# Zio_Eink_Display_1_54.net
KiCad netlist of a schematic drawn in EAGLE
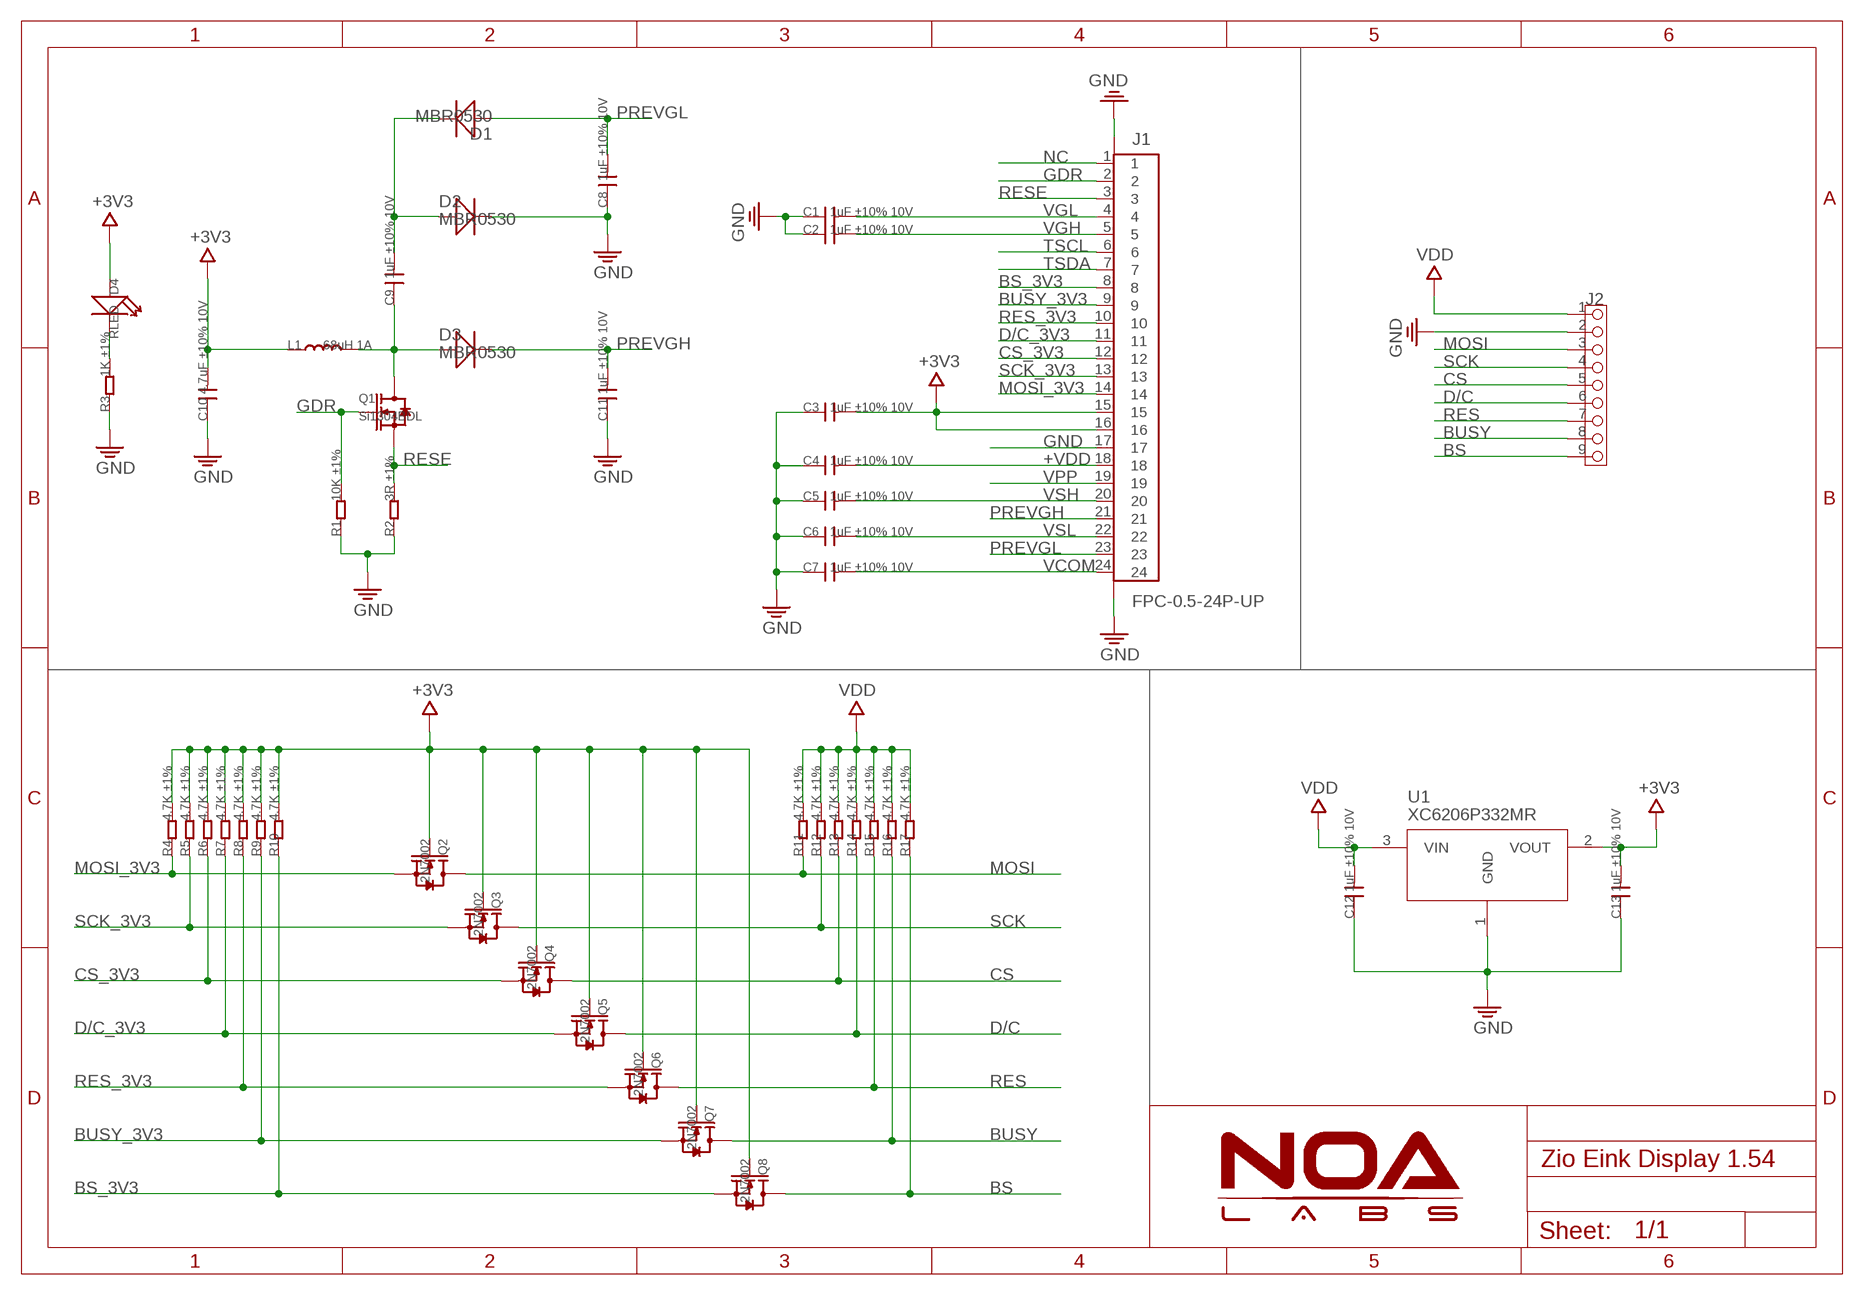
[diagram p0: schematic, sheet 1]

(export (version "E")
  (design (tool "Eeschema 10.0.6"))
  (components
    (comp (ref "C1")
      (value "1uF ±10% 10V")
      (footprint "eagle-import:0603")
      (libsource (lib "eagle-import") (part "C-0603"))
    )
    (comp (ref "C2")
      (value "1uF ±10% 10V")
      (footprint "eagle-import:0603")
      (libsource (lib "eagle-import") (part "C-0603"))
    )
    (comp (ref "C3")
      (value "1uF ±10% 10V")
      (footprint "eagle-import:0603")
      (libsource (lib "eagle-import") (part "C-0603"))
    )
    (comp (ref "C4")
      (value "1uF ±10% 10V")
      (footprint "eagle-import:0603")
      (libsource (lib "eagle-import") (part "C-0603"))
    )
    (comp (ref "C5")
      (value "1uF ±10% 10V")
      (footprint "eagle-import:0603")
      (libsource (lib "eagle-import") (part "C-0603"))
    )
    (comp (ref "C6")
      (value "1uF ±10% 10V")
      (footprint "eagle-import:0603")
      (libsource (lib "eagle-import") (part "C-0603"))
    )
    (comp (ref "C7")
      (value "1uF ±10% 10V")
      (footprint "eagle-import:0603")
      (libsource (lib "eagle-import") (part "C-0603"))
    )
    (comp (ref "C8")
      (value "1uF ±10% 10V")
      (footprint "eagle-import:0603")
      (libsource (lib "eagle-import") (part "C-0603"))
    )
    (comp (ref "C9")
      (value "1uF ±10% 10V")
      (footprint "eagle-import:0603")
      (libsource (lib "eagle-import") (part "C-0603"))
    )
    (comp (ref "C10")
      (value "4.7uF ±10% 10V")
      (footprint "eagle-import:0603")
      (libsource (lib "eagle-import") (part "C-0603"))
    )
    (comp (ref "C11")
      (value "1uF ±10% 10V")
      (footprint "eagle-import:0603")
      (libsource (lib "eagle-import") (part "C-0603"))
    )
    (comp (ref "C12")
      (value "1uF ±10% 10V")
      (footprint "eagle-import:0603")
      (libsource (lib "eagle-import") (part "C-0603"))
    )
    (comp (ref "C13")
      (value "1uF ±10% 10V")
      (footprint "eagle-import:0603")
      (libsource (lib "eagle-import") (part "C-0603"))
    )
    (comp (ref "D1")
      (value "MBR0530")
      (footprint "eagle-import:SOD123")
      (libsource (lib "eagle-import") (part "D'1206'"))
    )
    (comp (ref "D2")
      (value "MBR0530")
      (footprint "eagle-import:SOD123")
      (libsource (lib "eagle-import") (part "D'1206'"))
    )
    (comp (ref "D3")
      (value "MBR0530")
      (footprint "eagle-import:SOD123")
      (libsource (lib "eagle-import") (part "D'1206'"))
    )
    (comp (ref "D4")
      (value "RLED")
      (footprint "eagle-import:LED-0603")
      (libsource (lib "eagle-import") (part "LED'0603'"))
    )
    (comp (ref "J1")
      (value "FPC-0.5-24P-UP")
      (footprint "eagle-import:FPC-0.5-24P_UP")
      (libsource (lib "eagle-import") (part "FPC-0.5-24P-UP"))
    )
    (comp (ref "J2")
      (value "HEADER-9P2.54")
      (footprint "eagle-import:9P-2.54-SMD")
      (libsource (lib "eagle-import") (part "HEADER-9P2.54"))
    )
    (comp (ref "L1")
      (value "68uH 1A")
      (footprint "eagle-import:L3012")
      (libsource (lib "eagle-import") (part "L"))
    )
    (comp (ref "Q1")
      (value "Si1304BDL")
      (footprint "eagle-import:SOT-323")
      (libsource (lib "eagle-import") (part "MOSFET-N-323"))
    )
    (comp (ref "Q2")
      (value "2N7002")
      (footprint "eagle-import:SOT23")
      (libsource (lib "eagle-import") (part "MOSFET-N-SOT23"))
    )
    (comp (ref "Q3")
      (value "2N7002")
      (footprint "eagle-import:SOT23")
      (libsource (lib "eagle-import") (part "MOSFET-N-SOT23"))
    )
    (comp (ref "Q4")
      (value "2N7002")
      (footprint "eagle-import:SOT23")
      (libsource (lib "eagle-import") (part "MOSFET-N-SOT23"))
    )
    (comp (ref "Q5")
      (value "2N7002")
      (footprint "eagle-import:SOT23")
      (libsource (lib "eagle-import") (part "MOSFET-N-SOT23"))
    )
    (comp (ref "Q6")
      (value "2N7002")
      (footprint "eagle-import:SOT23")
      (libsource (lib "eagle-import") (part "MOSFET-N-SOT23"))
    )
    (comp (ref "Q7")
      (value "2N7002")
      (footprint "eagle-import:SOT23")
      (libsource (lib "eagle-import") (part "MOSFET-N-SOT23"))
    )
    (comp (ref "Q8")
      (value "2N7002")
      (footprint "eagle-import:SOT23")
      (libsource (lib "eagle-import") (part "MOSFET-N-SOT23"))
    )
    (comp (ref "R1")
      (value "10K ±1%")
      (footprint "eagle-import:0603")
      (libsource (lib "eagle-import") (part "R-0603"))
    )
    (comp (ref "R2")
      (value "3R ±1%")
      (footprint "eagle-import:0603")
      (libsource (lib "eagle-import") (part "R-0603"))
    )
    (comp (ref "R3")
      (value "1K ±1%")
      (footprint "eagle-import:0402")
      (libsource (lib "eagle-import") (part "R-0402"))
    )
    (comp (ref "R4")
      (value "4.7K ±1%")
      (footprint "eagle-import:0402")
      (libsource (lib "eagle-import") (part "R-0402"))
    )
    (comp (ref "R5")
      (value "4.7K ±1%")
      (footprint "eagle-import:0402")
      (libsource (lib "eagle-import") (part "R-0402"))
    )
    (comp (ref "R6")
      (value "4.7K ±1%")
      (footprint "eagle-import:0402")
      (libsource (lib "eagle-import") (part "R-0402"))
    )
    (comp (ref "R7")
      (value "4.7K ±1%")
      (footprint "eagle-import:0402")
      (libsource (lib "eagle-import") (part "R-0402"))
    )
    (comp (ref "R8")
      (value "4.7K ±1%")
      (footprint "eagle-import:0402")
      (libsource (lib "eagle-import") (part "R-0402"))
    )
    (comp (ref "R9")
      (value "4.7K ±1%")
      (footprint "eagle-import:0402")
      (libsource (lib "eagle-import") (part "R-0402"))
    )
    (comp (ref "R10")
      (value "4.7K ±1%")
      (footprint "eagle-import:0402")
      (libsource (lib "eagle-import") (part "R-0402"))
    )
    (comp (ref "R11")
      (value "4.7K ±1%")
      (footprint "eagle-import:0402")
      (libsource (lib "eagle-import") (part "R-0402"))
    )
    (comp (ref "R12")
      (value "4.7K ±1%")
      (footprint "eagle-import:0402")
      (libsource (lib "eagle-import") (part "R-0402"))
    )
    (comp (ref "R13")
      (value "4.7K ±1%")
      (footprint "eagle-import:0402")
      (libsource (lib "eagle-import") (part "R-0402"))
    )
    (comp (ref "R14")
      (value "4.7K ±1%")
      (footprint "eagle-import:0402")
      (libsource (lib "eagle-import") (part "R-0402"))
    )
    (comp (ref "R15")
      (value "4.7K ±1%")
      (footprint "eagle-import:0402")
      (libsource (lib "eagle-import") (part "R-0402"))
    )
    (comp (ref "R16")
      (value "4.7K ±1%")
      (footprint "eagle-import:0402")
      (libsource (lib "eagle-import") (part "R-0402"))
    )
    (comp (ref "R17")
      (value "4.7K ±1%")
      (footprint "eagle-import:0402")
      (libsource (lib "eagle-import") (part "R-0402"))
    )
    (comp (ref "U1")
      (value "XC6206P332MR")
      (footprint "eagle-import:SOT23")
      (libsource (lib "eagle-import") (part "XC6206MR"))
    )
  )
  (nets
    (net (code "1") (name "+3V3") (class "Default")
      (node (ref "C10") (pin "2") (pinfunction "2_2") (pintype "passive"))
      (node (ref "C13") (pin "2") (pinfunction "2_2") (pintype "passive"))
      (node (ref "C3") (pin "2") (pinfunction "2_2") (pintype "passive"))
      (node (ref "D4") (pin "+") (pinfunction "+_+") (pintype "passive"))
      (node (ref "J1") (pin "15") (pinfunction "15_15") (pintype "bidirectional"))
      (node (ref "J1") (pin "16") (pinfunction "16_16") (pintype "bidirectional"))
      (node (ref "L1") (pin "P$1") (pinfunction "1_P$1") (pintype "passive"))
      (node (ref "Q2") (pin "1") (pinfunction "G_1") (pintype "passive"))
      (node (ref "Q3") (pin "1") (pinfunction "G_1") (pintype "passive"))
      (node (ref "Q4") (pin "1") (pinfunction "G_1") (pintype "passive"))
      (node (ref "Q5") (pin "1") (pinfunction "G_1") (pintype "passive"))
      (node (ref "Q6") (pin "1") (pinfunction "G_1") (pintype "passive"))
      (node (ref "Q7") (pin "1") (pinfunction "G_1") (pintype "passive"))
      (node (ref "Q8") (pin "1") (pinfunction "G_1") (pintype "passive"))
      (node (ref "R10") (pin "2") (pinfunction "2_2") (pintype "passive"))
      (node (ref "R4") (pin "2") (pinfunction "2_2") (pintype "passive"))
      (node (ref "R5") (pin "2") (pinfunction "2_2") (pintype "passive"))
      (node (ref "R6") (pin "2") (pinfunction "2_2") (pintype "passive"))
      (node (ref "R7") (pin "2") (pinfunction "2_2") (pintype "passive"))
      (node (ref "R8") (pin "2") (pinfunction "2_2") (pintype "passive"))
      (node (ref "R9") (pin "2") (pinfunction "2_2") (pintype "passive"))
      (node (ref "U1") (pin "2") (pinfunction "VOUT_2") (pintype "bidirectional"))
    )
    (net (code "2") (name "/+VDD") (class "Default")
      (node (ref "C4") (pin "2") (pinfunction "2_2") (pintype "passive"))
      (node (ref "J1") (pin "18") (pinfunction "18_18") (pintype "bidirectional"))
    )
    (net (code "3") (name "/BS") (class "Default")
      (node (ref "J2") (pin "9") (pinfunction "9_9") (pintype "bidirectional"))
      (node (ref "Q8") (pin "3") (pinfunction "D_3") (pintype "passive"))
      (node (ref "R17") (pin "1") (pinfunction "1_1") (pintype "passive"))
    )
    (net (code "4") (name "/BS_3V3") (class "Default")
      (node (ref "J1") (pin "8") (pinfunction "8_8") (pintype "bidirectional"))
      (node (ref "Q8") (pin "2") (pinfunction "S_2") (pintype "passive"))
      (node (ref "R10") (pin "1") (pinfunction "1_1") (pintype "passive"))
    )
    (net (code "5") (name "/BUSY") (class "Default")
      (node (ref "J2") (pin "8") (pinfunction "8_8") (pintype "bidirectional"))
      (node (ref "Q7") (pin "3") (pinfunction "D_3") (pintype "passive"))
      (node (ref "R16") (pin "1") (pinfunction "1_1") (pintype "passive"))
    )
    (net (code "6") (name "/BUSY_3V3") (class "Default")
      (node (ref "J1") (pin "9") (pinfunction "9_9") (pintype "bidirectional"))
      (node (ref "Q7") (pin "2") (pinfunction "S_2") (pintype "passive"))
      (node (ref "R9") (pin "1") (pinfunction "1_1") (pintype "passive"))
    )
    (net (code "7") (name "/CS") (class "Default")
      (node (ref "J2") (pin "5") (pinfunction "5_5") (pintype "bidirectional"))
      (node (ref "Q4") (pin "3") (pinfunction "D_3") (pintype "passive"))
      (node (ref "R13") (pin "1") (pinfunction "1_1") (pintype "passive"))
    )
    (net (code "8") (name "/CS_3V3") (class "Default")
      (node (ref "J1") (pin "12") (pinfunction "12_12") (pintype "bidirectional"))
      (node (ref "Q4") (pin "2") (pinfunction "S_2") (pintype "passive"))
      (node (ref "R6") (pin "1") (pinfunction "1_1") (pintype "passive"))
    )
    (net (code "9") (name "/D{slash}C") (class "Default")
      (node (ref "J2") (pin "6") (pinfunction "6_6") (pintype "bidirectional"))
      (node (ref "Q5") (pin "3") (pinfunction "D_3") (pintype "passive"))
      (node (ref "R14") (pin "1") (pinfunction "1_1") (pintype "passive"))
    )
    (net (code "10") (name "/D{slash}C_3V3") (class "Default")
      (node (ref "J1") (pin "11") (pinfunction "11_11") (pintype "bidirectional"))
      (node (ref "Q5") (pin "2") (pinfunction "S_2") (pintype "passive"))
      (node (ref "R7") (pin "1") (pinfunction "1_1") (pintype "passive"))
    )
    (net (code "11") (name "/GDR") (class "Default")
      (node (ref "J1") (pin "2") (pinfunction "2_2") (pintype "bidirectional"))
      (node (ref "Q1") (pin "1") (pinfunction "G_1") (pintype "passive"))
      (node (ref "R1") (pin "2") (pinfunction "2_2") (pintype "passive"))
    )
    (net (code "12") (name "/MOSI") (class "Default")
      (node (ref "J2") (pin "3") (pinfunction "3_3") (pintype "bidirectional"))
      (node (ref "Q2") (pin "3") (pinfunction "D_3") (pintype "passive"))
      (node (ref "R11") (pin "1") (pinfunction "1_1") (pintype "passive"))
    )
    (net (code "13") (name "/MOSI_3V3") (class "Default")
      (node (ref "J1") (pin "14") (pinfunction "14_14") (pintype "bidirectional"))
      (node (ref "Q2") (pin "2") (pinfunction "S_2") (pintype "passive"))
      (node (ref "R4") (pin "1") (pinfunction "1_1") (pintype "passive"))
    )
    (net (code "14") (name "/NC") (class "Default")
      (node (ref "J1") (pin "1") (pinfunction "1_1") (pintype "bidirectional"))
    )
    (net (code "15") (name "/PREVGH") (class "Default")
      (node (ref "C11") (pin "2") (pinfunction "2_2") (pintype "passive"))
      (node (ref "D3") (pin "-") (pinfunction "-_-") (pintype "passive"))
      (node (ref "J1") (pin "21") (pinfunction "21_21") (pintype "bidirectional"))
    )
    (net (code "16") (name "/PREVGL") (class "Default")
      (node (ref "C8") (pin "2") (pinfunction "2_2") (pintype "passive"))
      (node (ref "D1") (pin "+") (pinfunction "+_+") (pintype "passive"))
      (node (ref "J1") (pin "23") (pinfunction "23_23") (pintype "bidirectional"))
    )
    (net (code "17") (name "/RES") (class "Default")
      (node (ref "J2") (pin "7") (pinfunction "7_7") (pintype "bidirectional"))
      (node (ref "Q6") (pin "3") (pinfunction "D_3") (pintype "passive"))
      (node (ref "R15") (pin "1") (pinfunction "1_1") (pintype "passive"))
    )
    (net (code "18") (name "/RESE") (class "Default")
      (node (ref "J1") (pin "3") (pinfunction "3_3") (pintype "bidirectional"))
      (node (ref "Q1") (pin "2") (pinfunction "S_2") (pintype "passive"))
      (node (ref "R2") (pin "2") (pinfunction "2_2") (pintype "passive"))
    )
    (net (code "19") (name "/RES_3V3") (class "Default")
      (node (ref "J1") (pin "10") (pinfunction "10_10") (pintype "bidirectional"))
      (node (ref "Q6") (pin "2") (pinfunction "S_2") (pintype "passive"))
      (node (ref "R8") (pin "1") (pinfunction "1_1") (pintype "passive"))
    )
    (net (code "20") (name "/SCK") (class "Default")
      (node (ref "J2") (pin "4") (pinfunction "4_4") (pintype "bidirectional"))
      (node (ref "Q3") (pin "3") (pinfunction "D_3") (pintype "passive"))
      (node (ref "R12") (pin "1") (pinfunction "1_1") (pintype "passive"))
    )
    (net (code "21") (name "/SCK_3V3") (class "Default")
      (node (ref "J1") (pin "13") (pinfunction "13_13") (pintype "bidirectional"))
      (node (ref "Q3") (pin "2") (pinfunction "S_2") (pintype "passive"))
      (node (ref "R5") (pin "1") (pinfunction "1_1") (pintype "passive"))
    )
    (net (code "22") (name "/TSCL") (class "Default")
      (node (ref "J1") (pin "6") (pinfunction "6_6") (pintype "bidirectional"))
    )
    (net (code "23") (name "/TSDA") (class "Default")
      (node (ref "J1") (pin "7") (pinfunction "7_7") (pintype "bidirectional"))
    )
    (net (code "24") (name "/VCOM") (class "Default")
      (node (ref "C7") (pin "2") (pinfunction "2_2") (pintype "passive"))
      (node (ref "J1") (pin "24") (pinfunction "24_24") (pintype "bidirectional"))
    )
    (net (code "25") (name "/VGH") (class "Default")
      (node (ref "C2") (pin "2") (pinfunction "2_2") (pintype "passive"))
      (node (ref "J1") (pin "5") (pinfunction "5_5") (pintype "bidirectional"))
    )
    (net (code "26") (name "/VGL") (class "Default")
      (node (ref "C1") (pin "2") (pinfunction "2_2") (pintype "passive"))
      (node (ref "J1") (pin "4") (pinfunction "4_4") (pintype "bidirectional"))
    )
    (net (code "27") (name "/VPP") (class "Default")
      (node (ref "J1") (pin "19") (pinfunction "19_19") (pintype "bidirectional"))
    )
    (net (code "28") (name "/VSH") (class "Default")
      (node (ref "C5") (pin "2") (pinfunction "2_2") (pintype "passive"))
      (node (ref "J1") (pin "20") (pinfunction "20_20") (pintype "bidirectional"))
    )
    (net (code "29") (name "/VSL") (class "Default")
      (node (ref "C6") (pin "2") (pinfunction "2_2") (pintype "passive"))
      (node (ref "J1") (pin "22") (pinfunction "22_22") (pintype "bidirectional"))
    )
    (net (code "30") (name "GND") (class "Default")
      (node (ref "C1") (pin "1") (pinfunction "1_1") (pintype "passive"))
      (node (ref "C10") (pin "1") (pinfunction "1_1") (pintype "passive"))
      (node (ref "C11") (pin "1") (pinfunction "1_1") (pintype "passive"))
      (node (ref "C12") (pin "1") (pinfunction "1_1") (pintype "passive"))
      (node (ref "C13") (pin "1") (pinfunction "1_1") (pintype "passive"))
      (node (ref "C2") (pin "1") (pinfunction "1_1") (pintype "passive"))
      (node (ref "C3") (pin "1") (pinfunction "1_1") (pintype "passive"))
      (node (ref "C4") (pin "1") (pinfunction "1_1") (pintype "passive"))
      (node (ref "C5") (pin "1") (pinfunction "1_1") (pintype "passive"))
      (node (ref "C6") (pin "1") (pinfunction "1_1") (pintype "passive"))
      (node (ref "C7") (pin "1") (pinfunction "1_1") (pintype "passive"))
      (node (ref "C8") (pin "1") (pinfunction "1_1") (pintype "passive"))
      (node (ref "D2") (pin "-") (pinfunction "-_-") (pintype "passive"))
      (node (ref "J1") (pin "17") (pinfunction "17_17") (pintype "bidirectional"))
      (node (ref "J1") (pin "25") (pinfunction "G1_25") (pintype "bidirectional"))
      (node (ref "J1") (pin "26") (pinfunction "G2_26") (pintype "bidirectional"))
      (node (ref "J2") (pin "2") (pinfunction "2_2") (pintype "bidirectional"))
      (node (ref "R1") (pin "1") (pinfunction "1_1") (pintype "passive"))
      (node (ref "R2") (pin "1") (pinfunction "1_1") (pintype "passive"))
      (node (ref "R3") (pin "1") (pinfunction "1_1") (pintype "passive"))
      (node (ref "U1") (pin "1") (pinfunction "GND_1") (pintype "bidirectional"))
    )
    (net (code "31") (name "Net-(C9-Pad2)") (class "Default")
      (node (ref "C9") (pin "2") (pinfunction "2_2") (pintype "passive"))
      (node (ref "D1") (pin "-") (pinfunction "-_-") (pintype "passive"))
      (node (ref "D2") (pin "+") (pinfunction "+_+") (pintype "passive"))
    )
    (net (code "32") (name "Net-(D4-Pad-)") (class "Default")
      (node (ref "D4") (pin "-") (pinfunction "-_-") (pintype "passive"))
      (node (ref "R3") (pin "2") (pinfunction "2_2") (pintype "passive"))
    )
    (net (code "33") (name "Net-(L1-2)") (class "Default")
      (node (ref "C9") (pin "1") (pinfunction "1_1") (pintype "passive"))
      (node (ref "D3") (pin "+") (pinfunction "+_+") (pintype "passive"))
      (node (ref "L1") (pin "P$2") (pinfunction "2_P$2") (pintype "passive"))
      (node (ref "Q1") (pin "3") (pinfunction "D_3") (pintype "passive"))
    )
    (net (code "34") (name "VDD") (class "Default")
      (node (ref "C12") (pin "2") (pinfunction "2_2") (pintype "passive"))
      (node (ref "J2") (pin "1") (pinfunction "1_1") (pintype "bidirectional"))
      (node (ref "R11") (pin "2") (pinfunction "2_2") (pintype "passive"))
      (node (ref "R12") (pin "2") (pinfunction "2_2") (pintype "passive"))
      (node (ref "R13") (pin "2") (pinfunction "2_2") (pintype "passive"))
      (node (ref "R14") (pin "2") (pinfunction "2_2") (pintype "passive"))
      (node (ref "R15") (pin "2") (pinfunction "2_2") (pintype "passive"))
      (node (ref "R16") (pin "2") (pinfunction "2_2") (pintype "passive"))
      (node (ref "R17") (pin "2") (pinfunction "2_2") (pintype "passive"))
      (node (ref "U1") (pin "3") (pinfunction "VIN_3") (pintype "bidirectional"))
    )
  )
)
